# Fri3D_2026_Audio.net
KiCad netlist of a schematic drawn in Altium Designer
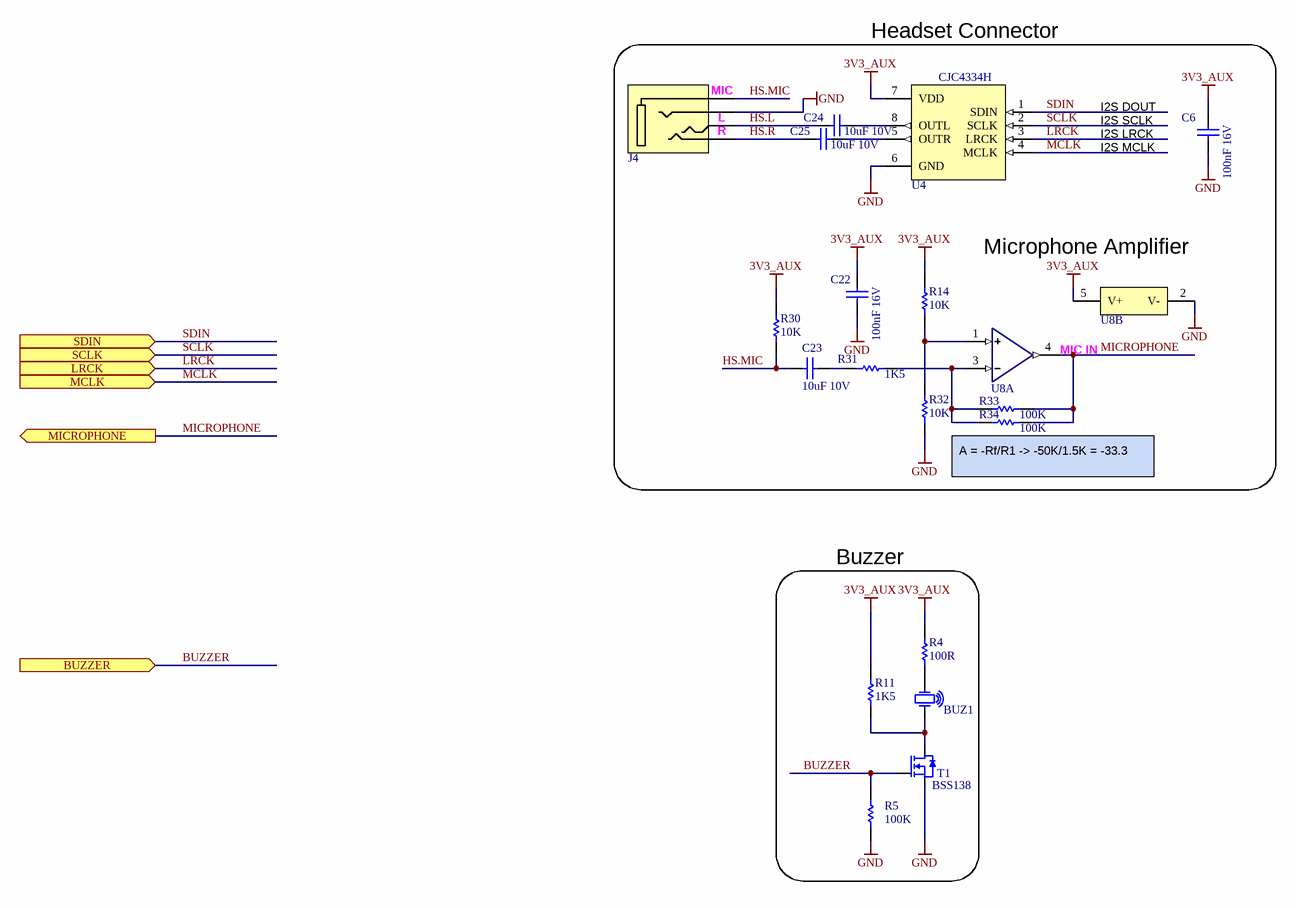
[diagram p0: Fri3D_2026_Audio.SchDoc]

(export (version "E")
  (design (tool "Eeschema 10.0.6"))
  (components
    (comp (ref "BUZ1")
      (value "12x12x3mm Piezo Buzzer Transducer 81dB")
      (footprint "CUI_CMT-1203-SMT")
      (description "Crystal Oscillator")
      (libsource (lib "Phyx_Components") (part "Buzzer"))
    )
    (comp (ref "C6")
      (value "100nF 16V")
      (footprint "C0603_N")
      (description "Capacitor Ceramic")
      (libsource (lib "Phyx_Components") (part "CAP_CERAMIC"))
    )
    (comp (ref "C22")
      (value "100nF 16V")
      (footprint "C0603_N")
      (description "Capacitor Ceramic")
      (libsource (lib "Phyx_Components") (part "CAP_CERAMIC"))
    )
    (comp (ref "C23")
      (value "10uF 10V")
      (footprint "C0805_N")
      (description "Capacitor Ceramic")
      (libsource (lib "Phyx_Components") (part "CAP_CERAMIC"))
    )
    (comp (ref "C24")
      (value "10uF 10V")
      (footprint "C0805_N")
      (description "Capacitor Ceramic")
      (libsource (lib "Phyx_Components") (part "CAP_CERAMIC"))
    )
    (comp (ref "C25")
      (value "10uF 10V")
      (footprint "C0805_N")
      (description "Capacitor Ceramic")
      (libsource (lib "Phyx_Components") (part "CAP_CERAMIC"))
    )
    (comp (ref "J4")
      (value "3.5mm jack, black, 4 contacts 15mm")
      (footprint "CAX_PJ-327F-5PS")
      (description "AUDIO JACK # 3.5 4c 15mm PJ-327F-5PS")
      (libsource (lib "Phyx_Components") (part "AUDIO_SRRT-1234"))
    )
    (comp (ref "R4")
      (value "100R")
      (footprint "R0603_N")
      (libsource (lib "Phyx_Components") (part "RESISTOR"))
    )
    (comp (ref "R5")
      (value "100K")
      (footprint "R0603_N")
      (libsource (lib "Phyx_Components") (part "RESISTOR"))
    )
    (comp (ref "R11")
      (value "1K5")
      (footprint "R0603_N")
      (libsource (lib "Phyx_Components") (part "RESISTOR"))
    )
    (comp (ref "R14")
      (value "10K")
      (footprint "R0603_N")
      (libsource (lib "Phyx_Components") (part "RESISTOR"))
    )
    (comp (ref "R30")
      (value "10K")
      (footprint "R0603_N")
      (libsource (lib "Phyx_Components") (part "RESISTOR"))
    )
    (comp (ref "R31")
      (value "1K5")
      (footprint "R0603_N")
      (libsource (lib "Phyx_Components") (part "RESISTOR"))
    )
    (comp (ref "R32")
      (value "10K")
      (footprint "R0603_N")
      (libsource (lib "Phyx_Components") (part "RESISTOR"))
    )
    (comp (ref "R33")
      (value "100K")
      (footprint "R0603_N")
      (libsource (lib "Phyx_Components") (part "RESISTOR"))
    )
    (comp (ref "R34")
      (value "100K")
      (footprint "R0603_N")
      (libsource (lib "Phyx_Components") (part "RESISTOR"))
    )
    (comp (ref "T1")
      (value "BSS138")
      (footprint "SOT23-3")
      (fields (field (name "Comment") "0.2A N-Ch MOSFET Vgs 3.2"))
      (libsource (lib "Phyx_Components") (part "N_MOSFET_GSD"))
    )
    (comp (ref "U4")
      (value "CJC4334H")
      (footprint "SOIC_N_8")
      (description "I2S Stereo DAC with 24-Bit, 192 kHz Stereo D/A Converter")
      (fields (field (name "Comment") "I²S 24bit 192kHz 3V~3.6V DAC"))
      (libsource (lib "Phyx_Components") (part "CSC_CJC4334H"))
    )
    (comp (ref "U8")
      (value "Single, 30-V, 1-MHz operational amplifier")
      (footprint "TI_DBV_R-PDSO-G5")
      (description "=Description")
      (libsource (lib "Phyx_Components") (part "TI_LM321"))
    )
  )
  (nets
    (net (code "1") (name "/BUZZER") (class "Default")
      (node (ref "R5") (pin "1") (pinfunction "1_1") (pintype "passive"))
      (node (ref "T1") (pin "1") (pinfunction "G_1") (pintype "passive"))
    )
    (net (code "2") (name "/HS.L") (class "Default")
      (node (ref "C24") (pin "1") (pinfunction "1_1") (pintype "passive"))
      (node (ref "J4") (pin "4") (pinfunction "Tip_4") (pintype "passive"))
    )
    (net (code "3") (name "/HS.MIC") (class "Default")
      (node (ref "C23") (pin "1") (pinfunction "1_1") (pintype "passive"))
      (node (ref "J4") (pin "1") (pinfunction "Sleeve_1") (pintype "passive"))
      (node (ref "R30") (pin "2") (pinfunction "2_2") (pintype "passive"))
    )
    (net (code "4") (name "/HS.R") (class "Default")
      (node (ref "C25") (pin "1") (pinfunction "1_1") (pintype "passive"))
      (node (ref "J4") (pin "3") (pinfunction "Ring_3") (pintype "passive"))
    )
    (net (code "5") (name "/LRCK") (class "Default")
      (node (ref "U4") (pin "3") (pinfunction "LRCK_3") (pintype "input"))
    )
    (net (code "6") (name "/MCLK") (class "Default")
      (node (ref "U4") (pin "4") (pinfunction "MCLK_4") (pintype "input"))
    )
    (net (code "7") (name "/MICROPHONE") (class "Default")
      (node (ref "R33") (pin "1") (pinfunction "1_1") (pintype "passive"))
      (node (ref "R34") (pin "1") (pinfunction "1_1") (pintype "passive"))
      (node (ref "U8") (pin "4") (pinfunction "OUT_4") (pintype "output"))
    )
    (net (code "8") (name "/SCLK") (class "Default")
      (node (ref "U4") (pin "2") (pinfunction "SCLK_2") (pintype "input"))
    )
    (net (code "9") (name "/SDIN") (class "Default")
      (node (ref "U4") (pin "1") (pinfunction "SDIN_1") (pintype "input"))
    )
    (net (code "10") (name "3V3_AUX") (class "Default")
      (node (ref "C22") (pin "1") (pinfunction "1_1") (pintype "passive"))
      (node (ref "C6") (pin "1") (pinfunction "1_1") (pintype "passive"))
      (node (ref "R11") (pin "2") (pinfunction "2_2") (pintype "passive"))
      (node (ref "R14") (pin "1") (pinfunction "1_1") (pintype "passive"))
      (node (ref "R30") (pin "1") (pinfunction "1_1") (pintype "passive"))
      (node (ref "R4") (pin "2") (pinfunction "2_2") (pintype "passive"))
      (node (ref "U4") (pin "7") (pinfunction "VDD_7") (pintype "power_in"))
      (node (ref "U8") (pin "5") (pinfunction "V+_5") (pintype "power_in"))
    )
    (net (code "11") (name "GND") (class "Default")
      (node (ref "C22") (pin "2") (pinfunction "2_2") (pintype "passive"))
      (node (ref "C6") (pin "2") (pinfunction "2_2") (pintype "passive"))
      (node (ref "J4") (pin "2") (pinfunction "Ring_2") (pintype "passive"))
      (node (ref "R32") (pin "2") (pinfunction "2_2") (pintype "passive"))
      (node (ref "R5") (pin "2") (pinfunction "2_2") (pintype "passive"))
      (node (ref "T1") (pin "2") (pinfunction "S_2") (pintype "passive"))
      (node (ref "U4") (pin "6") (pinfunction "GND_6") (pintype "power_in"))
      (node (ref "U8") (pin "2") (pinfunction "V-_2") (pintype "power_in"))
    )
    (net (code "12") (name "Net-(BUZ1-OSC1)") (class "Default")
      (node (ref "BUZ1") (pin "1") (pinfunction "OSC1_1") (pintype "passive"))
      (node (ref "R11") (pin "1") (pinfunction "1_1") (pintype "passive"))
      (node (ref "T1") (pin "3") (pinfunction "D_3") (pintype "passive"))
    )
    (net (code "13") (name "Net-(BUZ1-OSC2)") (class "Default")
      (node (ref "BUZ1") (pin "2") (pinfunction "OSC2_2") (pintype "passive"))
      (node (ref "R4") (pin "1") (pinfunction "1_1") (pintype "passive"))
    )
    (net (code "14") (name "Net-(C23-Pad2)") (class "Default")
      (node (ref "C23") (pin "2") (pinfunction "2_2") (pintype "passive"))
      (node (ref "R31") (pin "2") (pinfunction "2_2") (pintype "passive"))
    )
    (net (code "15") (name "Net-(U4-OUTL)") (class "Default")
      (node (ref "C24") (pin "2") (pinfunction "2_2") (pintype "passive"))
      (node (ref "U4") (pin "8") (pinfunction "OUTL_8") (pintype "output"))
    )
    (net (code "16") (name "Net-(U4-OUTR)") (class "Default")
      (node (ref "C25") (pin "2") (pinfunction "2_2") (pintype "passive"))
      (node (ref "U4") (pin "5") (pinfunction "OUTR_5") (pintype "output"))
    )
    (net (code "17") (name "Net-(U8A-+)") (class "Default")
      (node (ref "R14") (pin "2") (pinfunction "2_2") (pintype "passive"))
      (node (ref "R32") (pin "1") (pinfunction "1_1") (pintype "passive"))
      (node (ref "U8") (pin "1") (pinfunction "+_1") (pintype "input"))
    )
    (net (code "18") (name "Net-(U8A--)") (class "Default")
      (node (ref "R31") (pin "1") (pinfunction "1_1") (pintype "passive"))
      (node (ref "R33") (pin "2") (pinfunction "2_2") (pintype "passive"))
      (node (ref "R34") (pin "2") (pinfunction "2_2") (pintype "passive"))
      (node (ref "U8") (pin "3") (pinfunction "-_3") (pintype "input"))
    )
  )
)
